# IO_Expandor.net
KiCad netlist of a schematic drawn in Altium Designer
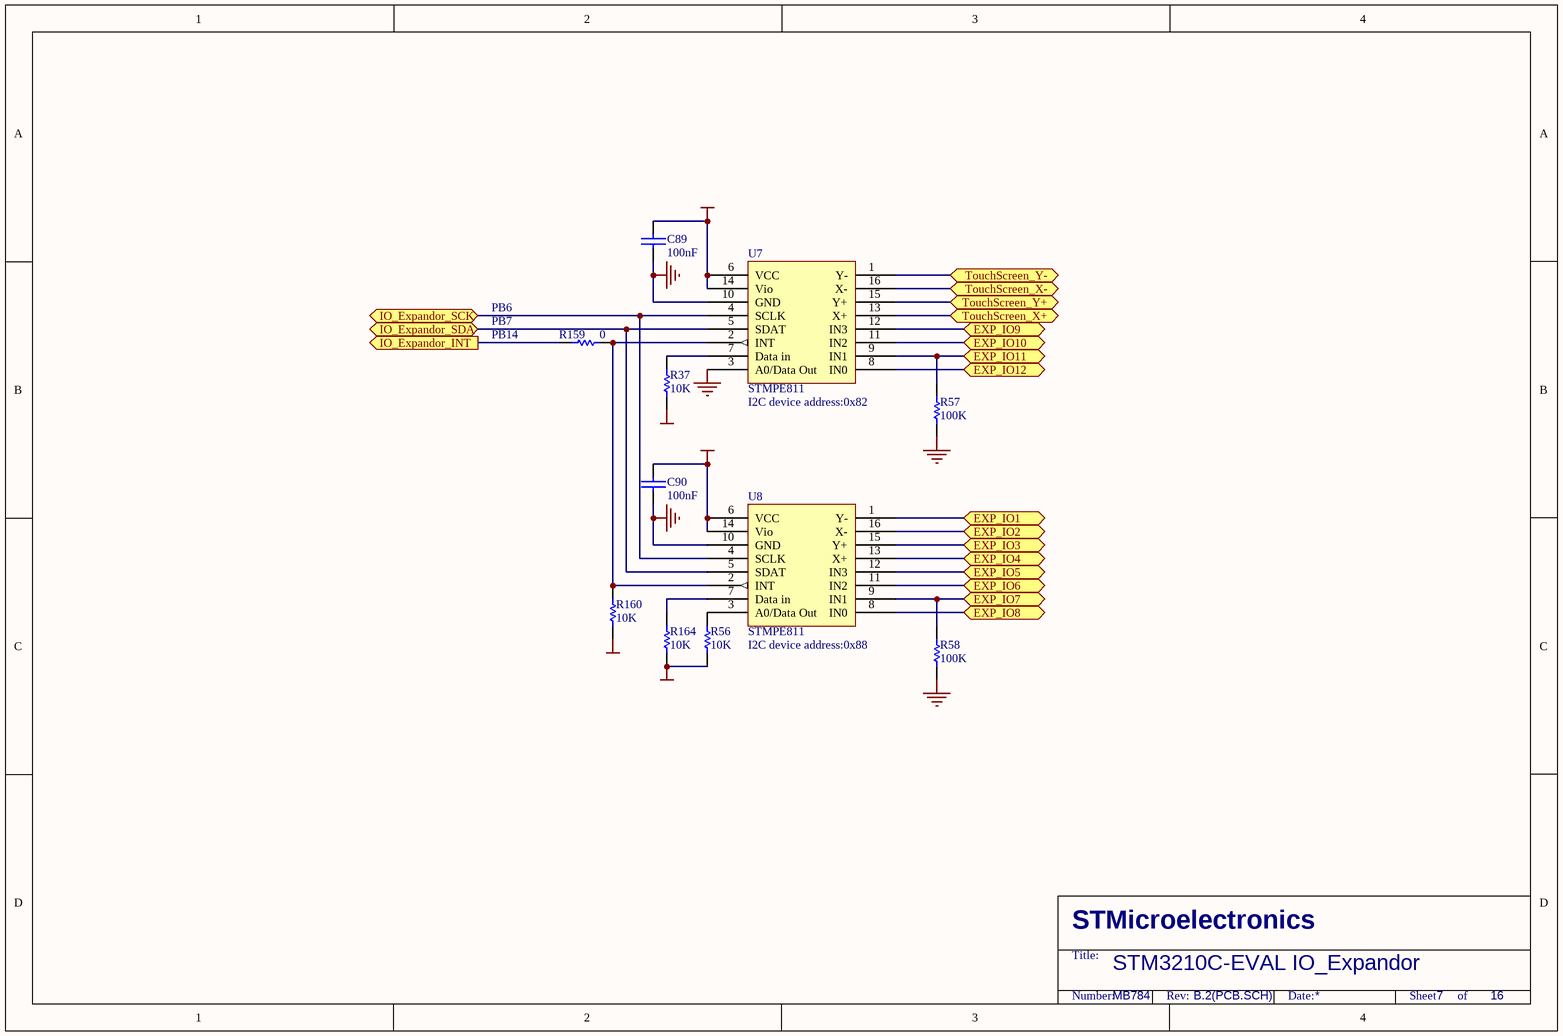
[diagram p0: IO_Expandor.SchDoc]

(export (version "E")
  (design (tool "Eeschema 10.0.6"))
  (components
    (comp (ref "C89")
      (value "100nF")
      (footprint "0603C")
      (description "Capacitor")
      (libsource (lib "*") (part "CAP"))
    )
    (comp (ref "C90")
      (value "100nF")
      (footprint "0603C")
      (description "Capacitor")
      (libsource (lib "*") (part "CAP"))
    )
    (comp (ref "R37")
      (value "10K")
      (footprint "0603R")
      (description "Resistor")
      (fields (field (name "PUBLISHER") "Altium Limited"))
      (libsource (lib "Miscellaneous Devices") (part "Res1"))
    )
    (comp (ref "R56")
      (value "10K")
      (footprint "0603R")
      (description "Resistor")
      (fields (field (name "PUBLISHER") "Altium Limited"))
      (libsource (lib "Miscellaneous Devices") (part "Res1"))
    )
    (comp (ref "R57")
      (value "100K")
      (footprint "0603R")
      (description "Resistor")
      (fields (field (name "PUBLISHER") "Altium Limited"))
      (libsource (lib "Miscellaneous Devices") (part "Res1"))
    )
    (comp (ref "R58")
      (value "100K")
      (footprint "0603R")
      (description "Resistor")
      (fields (field (name "PUBLISHER") "Altium Limited"))
      (libsource (lib "Miscellaneous Devices") (part "Res1"))
    )
    (comp (ref "R159")
      (value "0")
      (footprint "0603R")
      (description "Resistor")
      (fields (field (name "PUBLISHER") "Altium Limited"))
      (libsource (lib "Miscellaneous Devices") (part "Res1"))
    )
    (comp (ref "R160")
      (value "10K")
      (footprint "0603R")
      (description "Resistor")
      (fields (field (name "PUBLISHER") "Altium Limited"))
      (libsource (lib "Miscellaneous Devices") (part "Res1"))
    )
    (comp (ref "R164")
      (value "10K")
      (footprint "0603R")
      (description "Resistor")
      (fields (field (name "PUBLISHER") "Altium Limited"))
      (libsource (lib "Miscellaneous Devices") (part "Res1"))
    )
    (comp (ref "U7") (value "STMPE811") (footprint "QFN16(3X3)") (libsource (lib "MB784") (part "STMPE811")))
    (comp (ref "U8") (value "STMPE811") (footprint "QFN16(3X3)") (libsource (lib "MB784") (part "STMPE811")))
  )
  (nets
    (net (code "1") (name "+3V3") (class "Default")
      (node (ref "C89") (pin "1") (pinfunction "1_1") (pintype "passive"))
      (node (ref "C90") (pin "2") (pinfunction "2_2") (pintype "passive"))
      (node (ref "R160") (pin "2") (pinfunction "2_2") (pintype "passive"))
      (node (ref "R164") (pin "2") (pinfunction "2_2") (pintype "passive"))
      (node (ref "R37") (pin "2") (pinfunction "2_2") (pintype "passive"))
      (node (ref "R56") (pin "2") (pinfunction "2_2") (pintype "passive"))
      (node (ref "U7") (pin "14") (pinfunction "Vio_14") (pintype "passive"))
      (node (ref "U7") (pin "6") (pinfunction "VCC_6") (pintype "passive"))
      (node (ref "U8") (pin "14") (pinfunction "Vio_14") (pintype "passive"))
      (node (ref "U8") (pin "6") (pinfunction "VCC_6") (pintype "passive"))
    )
    (net (code "2") (name "/EXP_IO1") (class "Default")
      (node (ref "U8") (pin "1") (pinfunction "Y-_1") (pintype "passive"))
    )
    (net (code "3") (name "/EXP_IO2") (class "Default")
      (node (ref "U8") (pin "16") (pinfunction "X-_16") (pintype "passive"))
    )
    (net (code "4") (name "/EXP_IO3") (class "Default")
      (node (ref "U8") (pin "15") (pinfunction "Y+_15") (pintype "passive"))
    )
    (net (code "5") (name "/EXP_IO4") (class "Default")
      (node (ref "U8") (pin "13") (pinfunction "X+_13") (pintype "passive"))
    )
    (net (code "6") (name "/EXP_IO5") (class "Default")
      (node (ref "U8") (pin "12") (pinfunction "IN3_12") (pintype "passive"))
    )
    (net (code "7") (name "/EXP_IO6") (class "Default")
      (node (ref "U8") (pin "11") (pinfunction "IN2_11") (pintype "passive"))
    )
    (net (code "8") (name "/EXP_IO7") (class "Default")
      (node (ref "R58") (pin "1") (pinfunction "1_1") (pintype "passive"))
      (node (ref "U8") (pin "9") (pinfunction "IN1_9") (pintype "passive"))
    )
    (net (code "9") (name "/EXP_IO8") (class "Default")
      (node (ref "U8") (pin "8") (pinfunction "IN0_8") (pintype "passive"))
    )
    (net (code "10") (name "/EXP_IO9") (class "Default")
      (node (ref "U7") (pin "12") (pinfunction "IN3_12") (pintype "passive"))
    )
    (net (code "11") (name "/EXP_IO10") (class "Default")
      (node (ref "U7") (pin "11") (pinfunction "IN2_11") (pintype "passive"))
    )
    (net (code "12") (name "/EXP_IO11") (class "Default")
      (node (ref "R57") (pin "1") (pinfunction "1_1") (pintype "passive"))
      (node (ref "U7") (pin "9") (pinfunction "IN1_9") (pintype "passive"))
    )
    (net (code "13") (name "/EXP_IO12") (class "Default")
      (node (ref "U7") (pin "8") (pinfunction "IN0_8") (pintype "passive"))
    )
    (net (code "14") (name "/IO_Expandor_INT") (class "Default")
      (node (ref "R159") (pin "1") (pinfunction "1_1") (pintype "passive"))
    )
    (net (code "15") (name "/IO_Expandor_SCK") (class "Default")
      (node (ref "U7") (pin "4") (pinfunction "SCLK_4") (pintype "passive"))
      (node (ref "U8") (pin "4") (pinfunction "SCLK_4") (pintype "passive"))
    )
    (net (code "16") (name "/IO_Expandor_SDA") (class "Default")
      (node (ref "U7") (pin "5") (pinfunction "SDAT_5") (pintype "passive"))
      (node (ref "U8") (pin "5") (pinfunction "SDAT_5") (pintype "passive"))
    )
    (net (code "17") (name "/TouchScreen_X+") (class "Default")
      (node (ref "U7") (pin "13") (pinfunction "X+_13") (pintype "passive"))
    )
    (net (code "18") (name "/TouchScreen_X-") (class "Default")
      (node (ref "U7") (pin "16") (pinfunction "X-_16") (pintype "passive"))
    )
    (net (code "19") (name "/TouchScreen_Y+") (class "Default")
      (node (ref "U7") (pin "15") (pinfunction "Y+_15") (pintype "passive"))
    )
    (net (code "20") (name "/TouchScreen_Y-") (class "Default")
      (node (ref "U7") (pin "1") (pinfunction "Y-_1") (pintype "passive"))
    )
    (net (code "21") (name "GND") (class "Default")
      (node (ref "C89") (pin "2") (pinfunction "2_2") (pintype "passive"))
      (node (ref "C90") (pin "1") (pinfunction "1_1") (pintype "passive"))
      (node (ref "R57") (pin "2") (pinfunction "2_2") (pintype "passive"))
      (node (ref "R58") (pin "2") (pinfunction "2_2") (pintype "passive"))
      (node (ref "U7") (pin "10") (pinfunction "GND_10") (pintype "passive"))
      (node (ref "U7") (pin "3") (pinfunction "A0/Data_Out_3") (pintype "passive"))
      (node (ref "U8") (pin "10") (pinfunction "GND_10") (pintype "passive"))
    )
    (net (code "22") (name "Net-(U7-Data_in)") (class "Default")
      (node (ref "R37") (pin "1") (pinfunction "1_1") (pintype "passive"))
      (node (ref "U7") (pin "7") (pinfunction "Data_in_7") (pintype "passive"))
    )
    (net (code "23") (name "Net-(U7-INT)") (class "Default")
      (node (ref "R159") (pin "2") (pinfunction "2_2") (pintype "passive"))
      (node (ref "R160") (pin "1") (pinfunction "1_1") (pintype "passive"))
      (node (ref "U7") (pin "2") (pinfunction "INT_2") (pintype "output"))
      (node (ref "U8") (pin "2") (pinfunction "INT_2") (pintype "output"))
    )
    (net (code "24") (name "Net-(U8-A0{slash}Data_Out)") (class "Default")
      (node (ref "R56") (pin "1") (pinfunction "1_1") (pintype "passive"))
      (node (ref "U8") (pin "3") (pinfunction "A0/Data_Out_3") (pintype "passive"))
    )
    (net (code "25") (name "Net-(U8-Data_in)") (class "Default")
      (node (ref "R164") (pin "1") (pinfunction "1_1") (pintype "passive"))
      (node (ref "U8") (pin "7") (pinfunction "Data_in_7") (pintype "passive"))
    )
  )
)
